# Arduino_Connector.net
KiCad netlist of a schematic drawn in Altium Designer
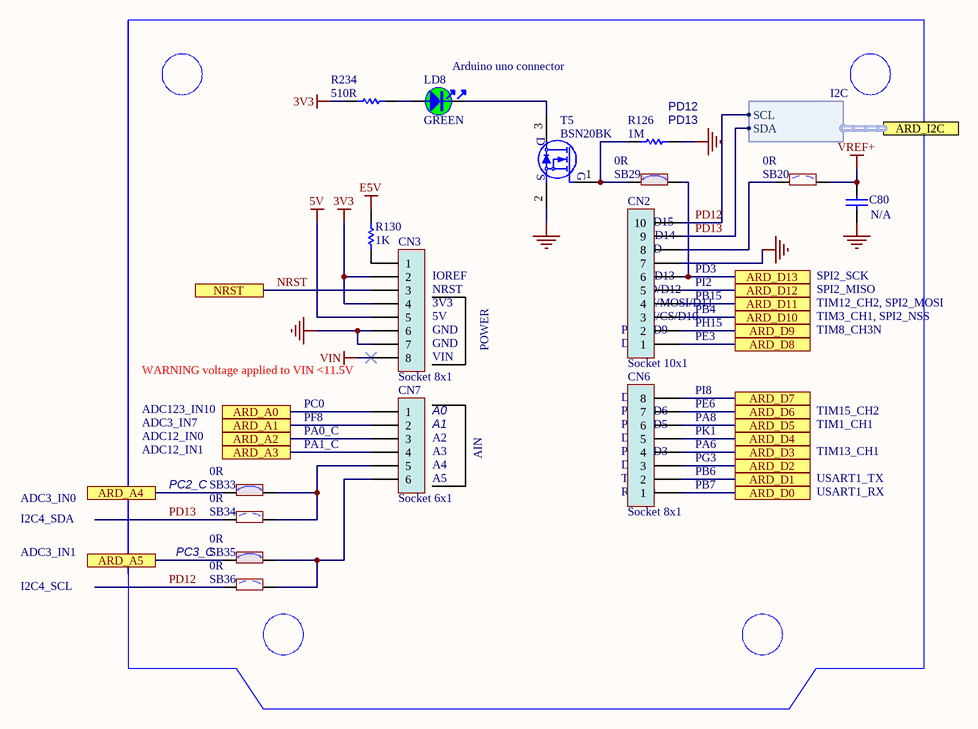
[diagram p0: Arduino_Connector.SchDoc]

(export (version "E")
  (design (tool "Eeschema 10.0.6"))
  (components
    (comp (ref "C80")
      (value "N/A")
      (footprint "C0603")
      (description "Capacitor, MLCC, 100nF, 16V, X7R, 10%, 0603, T=0,8mm")
      (fields
        (field (name "INTERNAL_PART_NUMBER") "MCD-00211")
        (field (name "MANUFACTURER_PART_NUMBER") "CC0603KRX7R7BB104")
        (field (name "PROVIDED_BY") "Subcon")
      )
      (libsource (lib "MCD_PARTS_database") (part "Capacitor"))
    )
    (comp (ref "CN2")
      (value "Socket 10x1")
      (footprint "CON_SAMTEC_SSW-110-22-X-S-VS")
      (description "Socket, 10x1, 2.54mm, VR, SMT, Height 9.78mm")
      (fields
        (field (name "INTERNAL_PART_NUMBER") "MCD-00301")
        (field (name "MANUFACTURER_PART_NUMBER") "SSW-110-22-L-S-VS")
        (field (name "PROVIDED_BY") "Subcon")
      )
      (libsource (lib "MCD_PARTS_database") (part "Socket 10x1"))
    )
    (comp (ref "CN3")
      (value "Socket 8x1")
      (footprint "CON_SAMTEC_SSW-108-22-X-S-VS")
      (description "Socket, 8x1, 2.54mm, VR, SMT, Height 9.78mm")
      (fields
        (field (name "INTERNAL_PART_NUMBER") "MCD-00300")
        (field (name "MANUFACTURER_PART_NUMBER") "SSW-108-22-L-S-VS")
        (field (name "PROVIDED_BY") "Subcon")
      )
      (libsource (lib "MCD_PARTS_database") (part "Socket 8x1"))
    )
    (comp (ref "CN6")
      (value "Socket 8x1")
      (footprint "CON_SAMTEC_SSW-108-22-X-S-VS")
      (description "Socket, 8x1, 2.54mm, VR, SMT, Height 9.78mm")
      (fields
        (field (name "INTERNAL_PART_NUMBER") "MCD-00300")
        (field (name "MANUFACTURER_PART_NUMBER") "SSW-108-22-L-S-VS")
        (field (name "PROVIDED_BY") "Subcon")
      )
      (libsource (lib "") (part "Socket 8x1_1"))
    )
    (comp (ref "CN7")
      (value "Socket 6x1")
      (footprint "CON_SAMTEC_SSW-106-22-X-S-VS")
      (description "Socket, 6x1, 2.54mm, VR, SMT, Height 9.78mm")
      (fields
        (field (name "INTERNAL_PART_NUMBER") "MCD-00299")
        (field (name "MANUFACTURER_PART_NUMBER") "SSW-106-22-L-S-VS")
        (field (name "PROVIDED_BY") "Subcon")
      )
      (libsource (lib "MCD_PARTS_database") (part "Socket 6x1"))
    )
    (comp (ref "LD8")
      (value "GREEN")
      (footprint "LED_0603_GREEN")
      (description "LED, Green, 2V, 25mA, 0603, SMD")
      (fields (field (name "INTERNAL_PART_NUMBER") "MCD-02900") (field (name "MANUFACTURER") "EVERLIGHT"))
      (libsource (lib "MCD_PARTS_database") (part "LED_green"))
    )
    (comp (ref "R126")
      (value "1M")
      (footprint "R0603")
      (description "Resistor,1M,0603,1%,1/10W")
      (fields
        (field (name "INTERNAL_PART_NUMBER") "MCD-00257")
        (field (name "MANUFACTURER_PART_NUMBER") "RC0603FR-071ML")
        (field (name "PROVIDED_BY") "Subcon")
      )
      (libsource (lib "MCD_PARTS_database") (part "Resistor"))
    )
    (comp (ref "R130")
      (value "1K")
      (footprint "R0603")
      (description "Resistor,1K,0603,1%,1/10W")
      (fields
        (field (name "INTERNAL_PART_NUMBER") "MCD-00070")
        (field (name "MANUFACTURER_PART_NUMBER") "RC0603FR-071KL")
        (field (name "PROVIDED_BY") "Subcon")
      )
      (libsource (lib "MCD_PARTS_database") (part "Resistor"))
    )
    (comp (ref "R234")
      (value "510R")
      (footprint "R0603")
      (description "Resistor,510R,0603,1%,1/10W")
      (fields
        (field (name "INTERNAL_PART_NUMBER") "MCD-00225")
        (field (name "MANUFACTURER_PART_NUMBER") "RC0603FR-07510RL")
        (field (name "PROVIDED_BY") "Subcon")
      )
      (libsource (lib "MCD_PARTS_database") (part "Resistor"))
    )
    (comp (ref "SB20")
      (value "0R")
      (footprint "SOLDER-BRIDGE_R0603-0R")
      (description "Solder Bridge OFF")
      (fields (field (name "INTERNAL_PART_NUMBER") "MCD-00072") (field (name "MANUFACTURER") "YAGEO"))
      (libsource (lib "MCD_PARTS_database") (part "SB_OFF"))
    )
    (comp (ref "SB29")
      (value "0R")
      (footprint "SOLDER-BRIDGE_R0603-0R")
      (description "Solder Bridge ON")
      (fields
        (field (name "INTERNAL_PART_NUMBER") "MCD-00071")
        (field (name "MANUFACTURER") "YAGEO")
        (field (name "PROVIDED_BY") "Subcon")
      )
      (libsource (lib "MCD_PARTS_database") (part "SB_ON"))
    )
    (comp (ref "SB33")
      (value "0R")
      (footprint "SOLDER-BRIDGE_R0603-0R")
      (description "Solder Bridge ON")
      (fields
        (field (name "INTERNAL_PART_NUMBER") "MCD-00071")
        (field (name "MANUFACTURER") "YAGEO")
        (field (name "PROVIDED_BY") "Subcon")
      )
      (libsource (lib "MCD_PARTS_database") (part "SB_ON"))
    )
    (comp (ref "SB34")
      (value "0R")
      (footprint "SOLDER-BRIDGE_R0603-0R")
      (description "Solder Bridge OFF")
      (fields (field (name "INTERNAL_PART_NUMBER") "MCD-00072") (field (name "MANUFACTURER") "YAGEO"))
      (libsource (lib "MCD_PARTS_database") (part "SB_OFF"))
    )
    (comp (ref "SB35")
      (value "0R")
      (footprint "SOLDER-BRIDGE_R0603-0R")
      (description "Solder Bridge ON")
      (fields
        (field (name "INTERNAL_PART_NUMBER") "MCD-00071")
        (field (name "MANUFACTURER") "YAGEO")
        (field (name "PROVIDED_BY") "Subcon")
      )
      (libsource (lib "MCD_PARTS_database") (part "SB_ON"))
    )
    (comp (ref "SB36")
      (value "0R")
      (footprint "SOLDER-BRIDGE_R0603-0R")
      (description "Solder Bridge OFF")
      (fields (field (name "INTERNAL_PART_NUMBER") "MCD-00072") (field (name "MANUFACTURER") "YAGEO"))
      (libsource (lib "MCD_PARTS_database") (part "SB_OFF"))
    )
    (comp (ref "T5")
      (value "BSN20BK")
      (footprint "MOS_SOT23")
      (description "Transistor, N-channel enhancement mode field-effect transistor")
      (fields (field (name "INTERNAL_PART_NUMBER") "MCD-01969") (field (name "MANUFACTURER") "NEXPERIA"))
      (libsource (lib "MCD_PARTS_database") (part "BSN20"))
    )
  )
  (nets
    (net (code "2") (name "/ARD_A0") (class "Default")
      (node (ref "CN7") (pin "1") (pinfunction "1_1") (pintype "passive"))
    )
    (net (code "3") (name "/ARD_A1") (class "Default")
      (node (ref "CN7") (pin "2") (pinfunction "2_2") (pintype "passive"))
    )
    (net (code "4") (name "/ARD_A2") (class "Default")
      (node (ref "CN7") (pin "3") (pinfunction "3_3") (pintype "passive"))
    )
    (net (code "5") (name "/ARD_A3") (class "Default")
      (node (ref "CN7") (pin "4") (pinfunction "4_4") (pintype "passive"))
    )
    (net (code "6") (name "/ARD_A4") (class "Default")
      (node (ref "SB33") (pin "1") (pinfunction "1_1") (pintype "passive"))
    )
    (net (code "7") (name "/ARD_A5") (class "Default")
      (node (ref "SB35") (pin "1") (pinfunction "1_1") (pintype "passive"))
    )
    (net (code "8") (name "/ARD_D0") (class "Default")
      (node (ref "CN6") (pin "1") (pinfunction "1_1") (pintype "passive"))
    )
    (net (code "9") (name "/ARD_D1") (class "Default")
      (node (ref "CN6") (pin "2") (pinfunction "2_2") (pintype "passive"))
    )
    (net (code "10") (name "/ARD_D2") (class "Default")
      (node (ref "CN6") (pin "3") (pinfunction "3_3") (pintype "passive"))
    )
    (net (code "11") (name "/ARD_D3") (class "Default")
      (node (ref "CN6") (pin "4") (pinfunction "4_4") (pintype "passive"))
    )
    (net (code "12") (name "/ARD_D4") (class "Default")
      (node (ref "CN6") (pin "5") (pinfunction "5_5") (pintype "passive"))
    )
    (net (code "13") (name "/ARD_D5") (class "Default")
      (node (ref "CN6") (pin "6") (pinfunction "6_6") (pintype "passive"))
    )
    (net (code "14") (name "/ARD_D6") (class "Default")
      (node (ref "CN6") (pin "7") (pinfunction "7_7") (pintype "passive"))
    )
    (net (code "15") (name "/ARD_D7") (class "Default")
      (node (ref "CN6") (pin "8") (pinfunction "8_8") (pintype "passive"))
    )
    (net (code "16") (name "/ARD_D8") (class "Default")
      (node (ref "CN2") (pin "1") (pinfunction "1_1") (pintype "passive"))
    )
    (net (code "17") (name "/ARD_D9") (class "Default")
      (node (ref "CN2") (pin "2") (pinfunction "2_2") (pintype "passive"))
    )
    (net (code "18") (name "/ARD_D10") (class "Default")
      (node (ref "CN2") (pin "3") (pinfunction "3_3") (pintype "passive"))
    )
    (net (code "19") (name "/ARD_D11") (class "Default")
      (node (ref "CN2") (pin "4") (pinfunction "4_4") (pintype "passive"))
    )
    (net (code "20") (name "/ARD_D12") (class "Default")
      (node (ref "CN2") (pin "5") (pinfunction "5_5") (pintype "passive"))
    )
    (net (code "21") (name "/ARD_D13") (class "Default")
      (node (ref "CN2") (pin "6") (pinfunction "6_6") (pintype "passive"))
      (node (ref "SB29") (pin "2") (pinfunction "2_2") (pintype "passive"))
    )
    (net (code "22") (name "/NRST") (class "Default")
      (node (ref "CN3") (pin "3") (pinfunction "3_3") (pintype "passive"))
    )
    (net (code "23") (name "/PD12") (class "Default")
      (node (ref "CN2") (pin "10") (pinfunction "10_10") (pintype "passive"))
      (node (ref "SB36") (pin "1") (pinfunction "1_1") (pintype "passive"))
    )
    (net (code "24") (name "/PD13") (class "Default")
      (node (ref "CN2") (pin "9") (pinfunction "9_9") (pintype "passive"))
      (node (ref "SB34") (pin "1") (pinfunction "1_1") (pintype "passive"))
    )
    (net (code "26") (name "3V3") (class "Default")
      (node (ref "CN3") (pin "2") (pinfunction "2_2") (pintype "passive"))
      (node (ref "CN3") (pin "4") (pinfunction "4_4") (pintype "passive"))
      (node (ref "R234") (pin "2") (pinfunction "2_2") (pintype "passive"))
    )
    (net (code "27") (name "5V") (class "Default")
      (node (ref "CN3") (pin "5") (pinfunction "5_5") (pintype "passive"))
    )
    (net (code "28") (name "E5V") (class "Default")
      (node (ref "R130") (pin "1") (pinfunction "1_1") (pintype "passive"))
    )
    (net (code "29") (name "GND") (class "Default")
      (node (ref "C80") (pin "1") (pinfunction "1_1") (pintype "passive"))
      (node (ref "CN2") (pin "7") (pinfunction "7_7") (pintype "passive"))
      (node (ref "CN3") (pin "6") (pinfunction "6_6") (pintype "passive"))
      (node (ref "CN3") (pin "7") (pinfunction "7_7") (pintype "passive"))
      (node (ref "R126") (pin "2") (pinfunction "2_2") (pintype "passive"))
      (node (ref "T5") (pin "2") (pinfunction "S_2") (pintype "passive"))
    )
    (net (code "30") (name "Net-(CN2-Pad8)") (class "Default")
      (node (ref "CN2") (pin "8") (pinfunction "8_8") (pintype "passive"))
      (node (ref "SB20") (pin "1") (pinfunction "1_1") (pintype "passive"))
    )
    (net (code "31") (name "Net-(CN3-Pad1)") (class "Default")
      (node (ref "CN3") (pin "1") (pinfunction "1_1") (pintype "passive"))
      (node (ref "R130") (pin "2") (pinfunction "2_2") (pintype "passive"))
    )
    (net (code "32") (name "Net-(CN7-Pad5)") (class "Default")
      (node (ref "CN7") (pin "5") (pinfunction "5_5") (pintype "passive"))
      (node (ref "SB33") (pin "2") (pinfunction "2_2") (pintype "passive"))
      (node (ref "SB34") (pin "2") (pinfunction "2_2") (pintype "passive"))
    )
    (net (code "33") (name "Net-(CN7-Pad6)") (class "Default")
      (node (ref "CN7") (pin "6") (pinfunction "6_6") (pintype "passive"))
      (node (ref "SB35") (pin "2") (pinfunction "2_2") (pintype "passive"))
      (node (ref "SB36") (pin "2") (pinfunction "2_2") (pintype "passive"))
    )
    (net (code "34") (name "Net-(LD8-Pad1)") (class "Default")
      (node (ref "LD8") (pin "1") (pintype "passive"))
      (node (ref "R234") (pin "1") (pinfunction "1_1") (pintype "passive"))
    )
    (net (code "35") (name "Net-(T5-D)") (class "Default")
      (node (ref "LD8") (pin "2") (pintype "passive"))
      (node (ref "T5") (pin "3") (pinfunction "D_3") (pintype "passive"))
    )
    (net (code "36") (name "Net-(T5-G)") (class "Default")
      (node (ref "R126") (pin "1") (pinfunction "1_1") (pintype "passive"))
      (node (ref "SB29") (pin "1") (pinfunction "1_1") (pintype "passive"))
      (node (ref "T5") (pin "1") (pinfunction "G_1") (pintype "passive"))
    )
    (net (code "37") (name "VIN") (class "Default")
      (node (ref "CN3") (pin "8") (pinfunction "8_8") (pintype "passive"))
    )
    (net (code "38") (name "VREF+") (class "Default")
      (node (ref "C80") (pin "2") (pinfunction "2_2") (pintype "passive"))
      (node (ref "SB20") (pin "2") (pinfunction "2_2") (pintype "passive"))
    )
  )
)
